# Qwiic_IMU_Bonobo.net
KiCad netlist of a schematic drawn in EAGLE
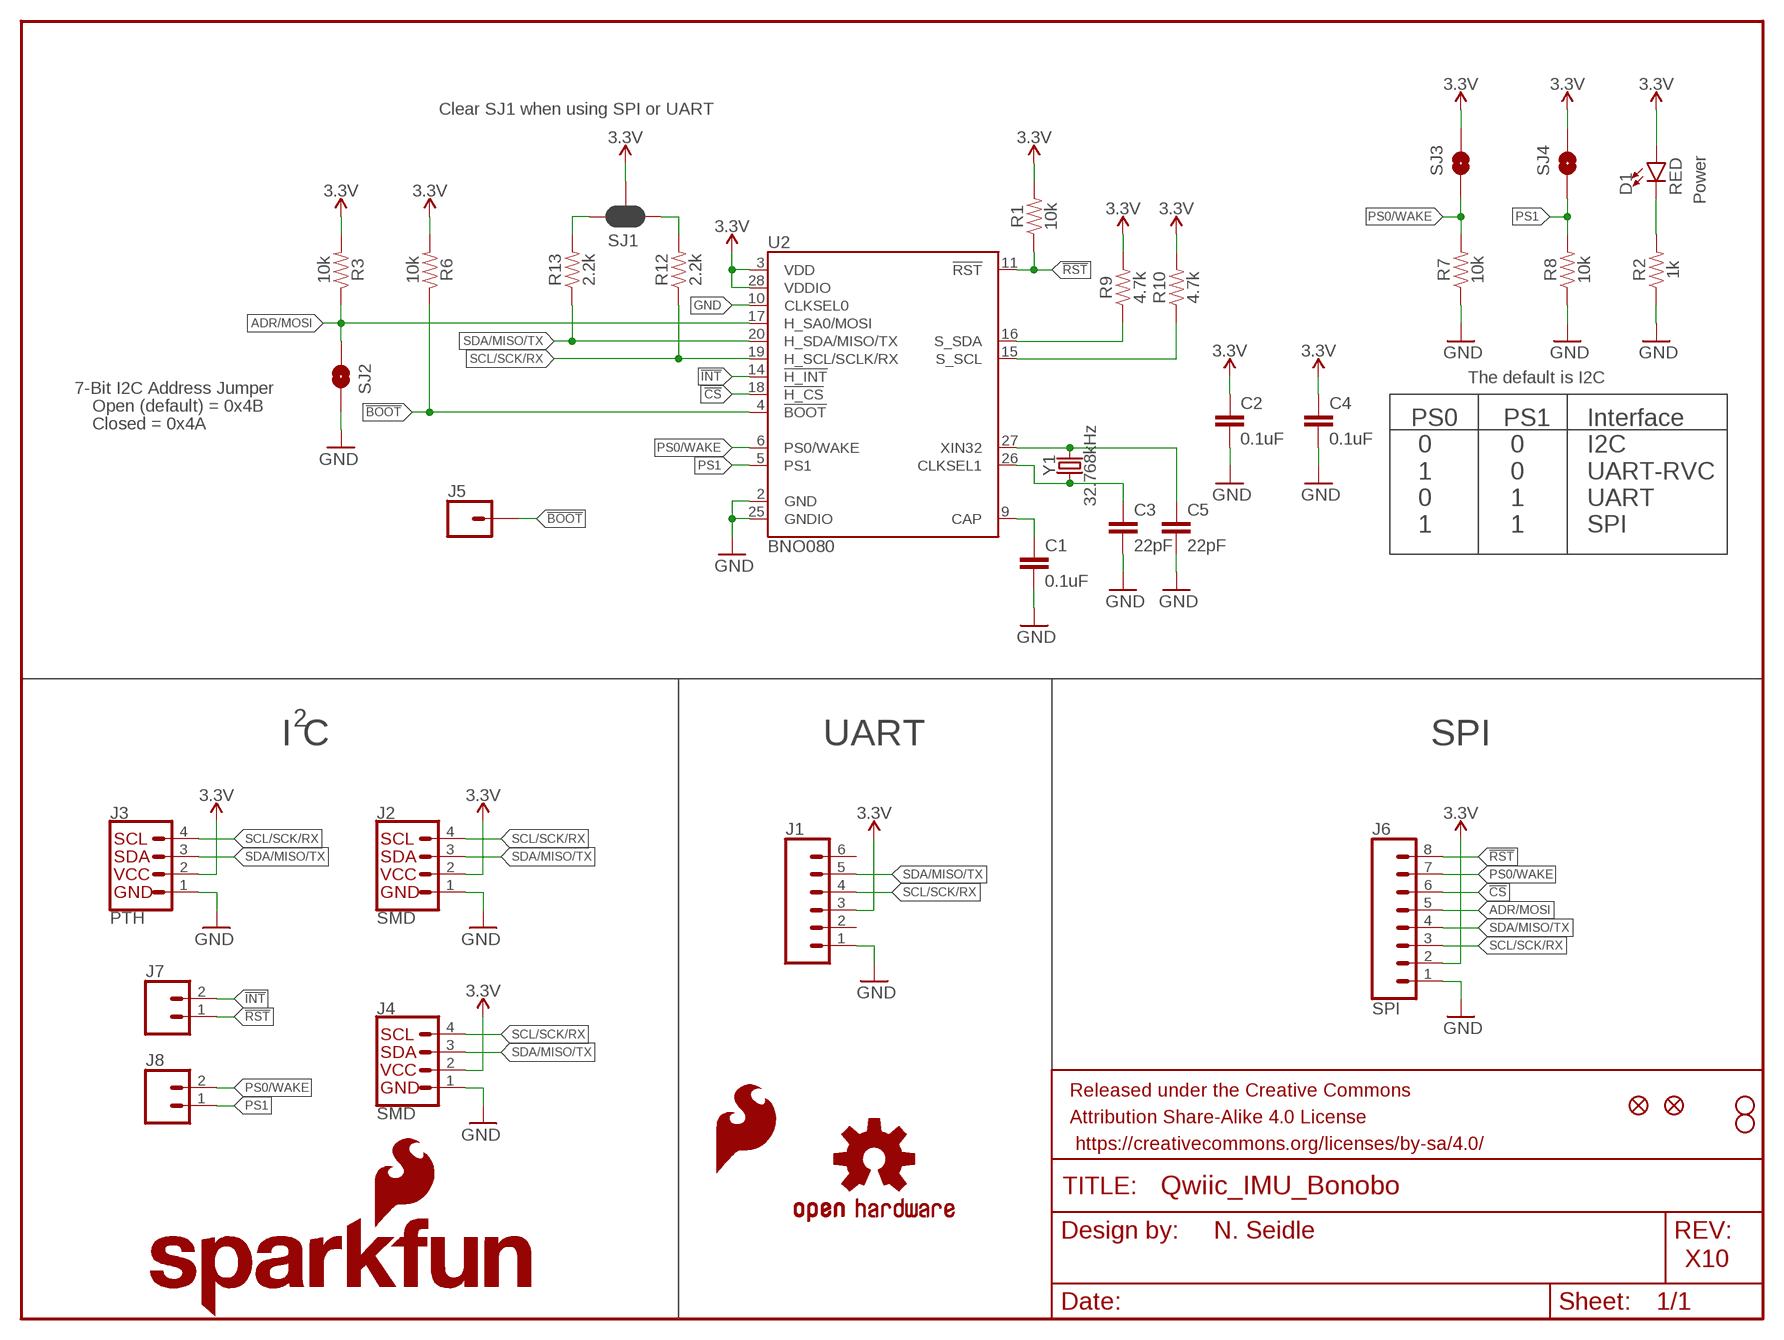
[diagram p0: schematic, sheet 1]

(export (version "E")
  (design (tool "Eeschema 10.0.6"))
  (components
    (comp (ref "C1")
      (value "0.1uF")
      (footprint "eagle-import:0603")
      (libsource (lib "eagle-import") (part "0.1UF-0603-25V-(+80/-20%)"))
    )
    (comp (ref "C2")
      (value "0.1uF")
      (footprint "eagle-import:0603")
      (libsource (lib "eagle-import") (part "0.1UF-0603-25V-(+80/-20%)"))
    )
    (comp (ref "C3")
      (value "22pF")
      (footprint "eagle-import:0603")
      (libsource (lib "eagle-import") (part "22PF-0603-50V-5%"))
    )
    (comp (ref "C4")
      (value "0.1uF")
      (footprint "eagle-import:0603")
      (libsource (lib "eagle-import") (part "0.1UF-0603-25V-(+80/-20%)"))
    )
    (comp (ref "C5")
      (value "22pF")
      (footprint "eagle-import:0603")
      (libsource (lib "eagle-import") (part "22PF-0603-50V-5%"))
    )
    (comp (ref "D1")
      (value "RED")
      (footprint "eagle-import:LED-0603")
      (libsource (lib "eagle-import") (part "LED-RED0603"))
    )
    (comp (ref "FRAME1")
      (value "FRAME-LETTER")
      (footprint "eagle-import:CREATIVE_COMMONS")
      (libsource (lib "eagle-import") (part "FRAME-LETTER"))
    )
    (comp (ref "J1")
      (value "CONN_06NO_SILK_FEMALE_PTH")
      (footprint "eagle-import:1X06_NO_SILK")
      (libsource (lib "eagle-import") (part "CONN_06NO_SILK_FEMALE_PTH"))
    )
    (comp (ref "J2")
      (value "SMD")
      (footprint "eagle-import:1X04_1MM_RA")
      (libsource (lib "eagle-import") (part "I2C_STANDARDJS-1MM"))
    )
    (comp (ref "J3")
      (value "PTH")
      (footprint "eagle-import:1X04_NO_SILK")
      (libsource (lib "eagle-import") (part "I2C_STANDARD_NO_SILK"))
    )
    (comp (ref "J4")
      (value "SMD")
      (footprint "eagle-import:1X04_1MM_RA")
      (libsource (lib "eagle-import") (part "I2C_STANDARDJS-1MM"))
    )
    (comp (ref "J5")
      (value "CONN_01PTH_NO_SILK_YES_STOP")
      (footprint "eagle-import:1X01_NO_SILK")
      (libsource (lib "eagle-import") (part "CONN_01PTH_NO_SILK_YES_STOP"))
    )
    (comp (ref "J6")
      (value "SPI")
      (footprint "eagle-import:1X08_NO_SILK")
      (libsource (lib "eagle-import") (part "CONN_08NO_SILK_FEMALE_PTH"))
    )
    (comp (ref "J7")
      (value "CONN_021X02_NO_SILK")
      (footprint "eagle-import:1X02_NO_SILK")
      (libsource (lib "eagle-import") (part "CONN_021X02_NO_SILK"))
    )
    (comp (ref "J8")
      (value "CONN_021X02_NO_SILK")
      (footprint "eagle-import:1X02_NO_SILK")
      (libsource (lib "eagle-import") (part "CONN_021X02_NO_SILK"))
    )
    (comp (ref "JP2")
      (value "FIDUCIALUFIDUCIAL")
      (footprint "eagle-import:MICRO-FIDUCIAL")
      (libsource (lib "eagle-import") (part "FIDUCIALUFIDUCIAL"))
    )
    (comp (ref "JP3")
      (value "STAND-OFF")
      (footprint "eagle-import:STAND-OFF")
      (libsource (lib "eagle-import") (part "STAND-OFF"))
    )
    (comp (ref "JP4")
      (value "STAND-OFF")
      (footprint "eagle-import:STAND-OFF")
      (libsource (lib "eagle-import") (part "STAND-OFF"))
    )
    (comp (ref "JP6")
      (value "FIDUCIALUFIDUCIAL")
      (footprint "eagle-import:MICRO-FIDUCIAL")
      (libsource (lib "eagle-import") (part "FIDUCIALUFIDUCIAL"))
    )
    (comp (ref "LOGO1")
      (value "OSHW-LOGOMINI")
      (footprint "eagle-import:OSHW-LOGO-MINI")
      (libsource (lib "eagle-import") (part "OSHW-LOGOMINI"))
    )
    (comp (ref "LOGO4")
      (value "SFE_LOGO_FLAME.1_INCH")
      (footprint "eagle-import:SFE_LOGO_FLAME_.1")
      (libsource (lib "eagle-import") (part "SFE_LOGO_FLAME.1_INCH"))
    )
    (comp (ref "LOGO5")
      (value "SFE_LOGO_NAME_FLAME.1_INCH")
      (footprint "eagle-import:SFE_LOGO_NAME_FLAME_.1")
      (libsource (lib "eagle-import") (part "SFE_LOGO_NAME_FLAME.1_INCH"))
    )
    (comp (ref "R1")
      (value "10k")
      (footprint "eagle-import:0603")
      (libsource (lib "eagle-import") (part "10KOHM-0603-1/10W-1%"))
    )
    (comp (ref "R2")
      (value "1k")
      (footprint "eagle-import:0603")
      (libsource (lib "eagle-import") (part "1KOHM-0603-1/10W-1%"))
    )
    (comp (ref "R3")
      (value "10k")
      (footprint "eagle-import:0603")
      (libsource (lib "eagle-import") (part "10KOHM-0603-1/10W-1%"))
    )
    (comp (ref "R6")
      (value "10k")
      (footprint "eagle-import:0603")
      (libsource (lib "eagle-import") (part "10KOHM-0603-1/10W-1%"))
    )
    (comp (ref "R7")
      (value "10k")
      (footprint "eagle-import:0603")
      (libsource (lib "eagle-import") (part "10KOHM-0603-1/10W-1%"))
    )
    (comp (ref "R8")
      (value "10k")
      (footprint "eagle-import:0603")
      (libsource (lib "eagle-import") (part "10KOHM-0603-1/10W-1%"))
    )
    (comp (ref "R9")
      (value "4.7k")
      (footprint "eagle-import:0603")
      (libsource (lib "eagle-import") (part "4.7KOHM-0603-1/10W-1%"))
    )
    (comp (ref "R10")
      (value "4.7k")
      (footprint "eagle-import:0603")
      (libsource (lib "eagle-import") (part "4.7KOHM-0603-1/10W-1%"))
    )
    (comp (ref "R12")
      (value "2.2k")
      (footprint "eagle-import:0603")
      (libsource (lib "eagle-import") (part "2.2KOHM-0603-1/10W-1%"))
    )
    (comp (ref "R13")
      (value "2.2k")
      (footprint "eagle-import:0603")
      (libsource (lib "eagle-import") (part "2.2KOHM-0603-1/10W-1%"))
    )
    (comp (ref "SJ1")
      (value "JUMPER-SMT_3_2-NC_PASTE_SILK")
      (footprint "eagle-import:SMT-JUMPER_3_2-NC_PASTE_SILK")
      (libsource (lib "eagle-import") (part "JUMPER-SMT_3_2-NC_PASTE_SILK"))
    )
    (comp (ref "SJ2")
      (value "SOLDERJUMPERNO")
      (footprint "eagle-import:SJ_2S-NO")
      (libsource (lib "eagle-import") (part "SOLDERJUMPERNO"))
    )
    (comp (ref "SJ3")
      (value "SOLDERJUMPERNO")
      (footprint "eagle-import:SJ_2S-NO")
      (libsource (lib "eagle-import") (part "SOLDERJUMPERNO"))
    )
    (comp (ref "SJ4")
      (value "SOLDERJUMPERNO")
      (footprint "eagle-import:SJ_2S-NO")
      (libsource (lib "eagle-import") (part "SOLDERJUMPERNO"))
    )
    (comp (ref "U2")
      (value "BNO080")
      (footprint "eagle-import:LGA-28")
      (libsource (lib "eagle-import") (part "BNO080"))
    )
    (comp (ref "Y1")
      (value "32.768kHz")
      (footprint "eagle-import:CRYSTAL-SMD-3.2X1.5MM")
      (libsource (lib "eagle-import") (part "CRYSTAL-32.768KHZSMD-3.2X1.5"))
    )
  )
  (nets
    (net (code "1") (name "/~{BOOT}") (class "Default")
      (node (ref "J5") (pin "1") (pinfunction "1_1") (pintype "passive"))
      (node (ref "R6") (pin "1") (pinfunction "1_1") (pintype "passive"))
      (node (ref "U2") (pin "4") (pinfunction "~{BOOT}_4") (pintype "bidirectional"))
    )
    (net (code "2") (name "/~{CS}") (class "Default")
      (node (ref "J6") (pin "6") (pinfunction "6_6") (pintype "passive"))
      (node (ref "U2") (pin "18") (pinfunction "~{H_CS}_18") (pintype "bidirectional"))
    )
    (net (code "3") (name "/~{INT}") (class "Default")
      (node (ref "J7") (pin "2") (pinfunction "2_2") (pintype "passive"))
      (node (ref "U2") (pin "14") (pinfunction "~{H_INT}_14") (pintype "bidirectional"))
    )
    (net (code "4") (name "/~{RST}") (class "Default")
      (node (ref "J6") (pin "8") (pinfunction "8_8") (pintype "passive"))
      (node (ref "J7") (pin "1") (pinfunction "1_1") (pintype "passive"))
      (node (ref "R1") (pin "1") (pinfunction "1_1") (pintype "passive"))
      (node (ref "U2") (pin "11") (pinfunction "~{RST}_11") (pintype "bidirectional"))
    )
    (net (code "5") (name "3.3V") (class "Default")
      (node (ref "C2") (pin "1") (pinfunction "1_1") (pintype "passive"))
      (node (ref "C4") (pin "1") (pinfunction "1_1") (pintype "passive"))
      (node (ref "D1") (pin "A") (pinfunction "A_A") (pintype "passive"))
      (node (ref "J1") (pin "3") (pinfunction "3_3") (pintype "passive"))
      (node (ref "J2") (pin "2") (pinfunction "VCC_2") (pintype "power_in"))
      (node (ref "J3") (pin "2") (pinfunction "VCC_2") (pintype "power_in"))
      (node (ref "J4") (pin "2") (pinfunction "VCC_2") (pintype "power_in"))
      (node (ref "J6") (pin "2") (pinfunction "2_2") (pintype "passive"))
      (node (ref "R1") (pin "2") (pinfunction "2_2") (pintype "passive"))
      (node (ref "R10") (pin "2") (pinfunction "2_2") (pintype "passive"))
      (node (ref "R3") (pin "2") (pinfunction "2_2") (pintype "passive"))
      (node (ref "R6") (pin "2") (pinfunction "2_2") (pintype "passive"))
      (node (ref "R9") (pin "2") (pinfunction "2_2") (pintype "passive"))
      (node (ref "SJ1") (pin "2") (pinfunction "2_2") (pintype "passive"))
      (node (ref "SJ3") (pin "1") (pinfunction "1_1") (pintype "passive"))
      (node (ref "SJ4") (pin "1") (pinfunction "1_1") (pintype "passive"))
      (node (ref "U2") (pin "28") (pinfunction "VDDIO_28") (pintype "bidirectional"))
      (node (ref "U2") (pin "3") (pinfunction "VDD_3") (pintype "bidirectional"))
    )
    (net (code "6") (name "ADR{slash}MOSI") (class "Default")
      (node (ref "J6") (pin "5") (pinfunction "5_5") (pintype "passive"))
      (node (ref "R3") (pin "1") (pinfunction "1_1") (pintype "passive"))
      (node (ref "SJ2") (pin "2") (pinfunction "2_2") (pintype "passive"))
      (node (ref "U2") (pin "17") (pinfunction "H_SA0/MOSI_17") (pintype "bidirectional"))
    )
    (net (code "7") (name "GND") (class "Default")
      (node (ref "C1") (pin "2") (pinfunction "2_2") (pintype "passive"))
      (node (ref "C2") (pin "2") (pinfunction "2_2") (pintype "passive"))
      (node (ref "C3") (pin "2") (pinfunction "2_2") (pintype "passive"))
      (node (ref "C4") (pin "2") (pinfunction "2_2") (pintype "passive"))
      (node (ref "C5") (pin "2") (pinfunction "2_2") (pintype "passive"))
      (node (ref "J1") (pin "1") (pinfunction "1_1") (pintype "passive"))
      (node (ref "J2") (pin "1") (pinfunction "GND_1") (pintype "power_in"))
      (node (ref "J3") (pin "1") (pinfunction "GND_1") (pintype "power_in"))
      (node (ref "J4") (pin "1") (pinfunction "GND_1") (pintype "power_in"))
      (node (ref "J6") (pin "1") (pinfunction "1_1") (pintype "passive"))
      (node (ref "R2") (pin "1") (pinfunction "1_1") (pintype "passive"))
      (node (ref "R7") (pin "1") (pinfunction "1_1") (pintype "passive"))
      (node (ref "R8") (pin "1") (pinfunction "1_1") (pintype "passive"))
      (node (ref "SJ2") (pin "1") (pinfunction "1_1") (pintype "passive"))
      (node (ref "U2") (pin "10") (pinfunction "CLKSEL0_10") (pintype "bidirectional"))
      (node (ref "U2") (pin "2") (pinfunction "GND_2") (pintype "bidirectional"))
      (node (ref "U2") (pin "25") (pinfunction "GNDIO_25") (pintype "bidirectional"))
    )
    (net (code "8") (name "Net-(D1-PadC)") (class "Default")
      (node (ref "D1") (pin "C") (pinfunction "C_C") (pintype "passive"))
      (node (ref "R2") (pin "2") (pinfunction "2_2") (pintype "passive"))
    )
    (net (code "9") (name "Net-(R12-Pad2)") (class "Default")
      (node (ref "R12") (pin "2") (pinfunction "2_2") (pintype "passive"))
      (node (ref "SJ1") (pin "1") (pinfunction "1_1") (pintype "passive"))
    )
    (net (code "10") (name "Net-(R13-Pad2)") (class "Default")
      (node (ref "R13") (pin "2") (pinfunction "2_2") (pintype "passive"))
      (node (ref "SJ1") (pin "3") (pinfunction "3_3") (pintype "passive"))
    )
    (net (code "11") (name "Net-(U2-CAP)") (class "Default")
      (node (ref "C1") (pin "1") (pinfunction "1_1") (pintype "passive"))
      (node (ref "U2") (pin "9") (pinfunction "CAP_9") (pintype "bidirectional"))
    )
    (net (code "12") (name "Net-(U2-CLKSEL1)") (class "Default")
      (node (ref "C3") (pin "1") (pinfunction "1_1") (pintype "passive"))
      (node (ref "U2") (pin "26") (pinfunction "CLKSEL1_26") (pintype "bidirectional"))
      (node (ref "Y1") (pin "P$1") (pinfunction "1_P$1") (pintype "passive"))
    )
    (net (code "13") (name "Net-(U2-S_SCL)") (class "Default")
      (node (ref "R10") (pin "1") (pinfunction "1_1") (pintype "passive"))
      (node (ref "U2") (pin "15") (pinfunction "S_SCL_15") (pintype "bidirectional"))
    )
    (net (code "14") (name "Net-(U2-S_SDA)") (class "Default")
      (node (ref "R9") (pin "1") (pinfunction "1_1") (pintype "passive"))
      (node (ref "U2") (pin "16") (pinfunction "S_SDA_16") (pintype "bidirectional"))
    )
    (net (code "15") (name "Net-(U2-XIN32)") (class "Default")
      (node (ref "C5") (pin "1") (pinfunction "1_1") (pintype "passive"))
      (node (ref "U2") (pin "27") (pinfunction "XIN32_27") (pintype "bidirectional"))
      (node (ref "Y1") (pin "P$2") (pinfunction "2_P$2") (pintype "passive"))
    )
    (net (code "16") (name "PS0{slash}WAKE") (class "Default")
      (node (ref "J6") (pin "7") (pinfunction "7_7") (pintype "passive"))
      (node (ref "J8") (pin "2") (pinfunction "2_2") (pintype "passive"))
      (node (ref "R7") (pin "2") (pinfunction "2_2") (pintype "passive"))
      (node (ref "SJ3") (pin "2") (pinfunction "2_2") (pintype "passive"))
      (node (ref "U2") (pin "6") (pinfunction "PS0/WAKE_6") (pintype "bidirectional"))
    )
    (net (code "17") (name "PS1") (class "Default")
      (node (ref "J8") (pin "1") (pinfunction "1_1") (pintype "passive"))
      (node (ref "R8") (pin "2") (pinfunction "2_2") (pintype "passive"))
      (node (ref "SJ4") (pin "2") (pinfunction "2_2") (pintype "passive"))
      (node (ref "U2") (pin "5") (pinfunction "PS1_5") (pintype "bidirectional"))
    )
    (net (code "18") (name "SCL{slash}SCK{slash}RX") (class "Default")
      (node (ref "J1") (pin "4") (pinfunction "4_4") (pintype "passive"))
      (node (ref "J2") (pin "4") (pinfunction "SCL_4") (pintype "passive"))
      (node (ref "J3") (pin "4") (pinfunction "SCL_4") (pintype "passive"))
      (node (ref "J4") (pin "4") (pinfunction "SCL_4") (pintype "passive"))
      (node (ref "J6") (pin "3") (pinfunction "3_3") (pintype "passive"))
      (node (ref "R12") (pin "1") (pinfunction "1_1") (pintype "passive"))
      (node (ref "U2") (pin "19") (pinfunction "H_SCL/SCLK/RX_19") (pintype "bidirectional"))
    )
    (net (code "19") (name "SDA{slash}MISO{slash}TX") (class "Default")
      (node (ref "J1") (pin "5") (pinfunction "5_5") (pintype "passive"))
      (node (ref "J2") (pin "3") (pinfunction "SDA_3") (pintype "passive"))
      (node (ref "J3") (pin "3") (pinfunction "SDA_3") (pintype "passive"))
      (node (ref "J4") (pin "3") (pinfunction "SDA_3") (pintype "passive"))
      (node (ref "J6") (pin "4") (pinfunction "4_4") (pintype "passive"))
      (node (ref "R13") (pin "1") (pinfunction "1_1") (pintype "passive"))
      (node (ref "U2") (pin "20") (pinfunction "H_SDA/MISO/TX_20") (pintype "bidirectional"))
    )
    (net (code "20") (name "unconnected-(J1-Pad2)") (class "Default")
      (node (ref "J1") (pin "2") (pinfunction "2_2") (pintype "passive"))
    )
    (net (code "21") (name "unconnected-(J1-Pad6)") (class "Default")
      (node (ref "J1") (pin "6") (pinfunction "6_6") (pintype "passive"))
    )
  )
)
